# usb2.net
KiCad netlist of a schematic drawn in EAGLE
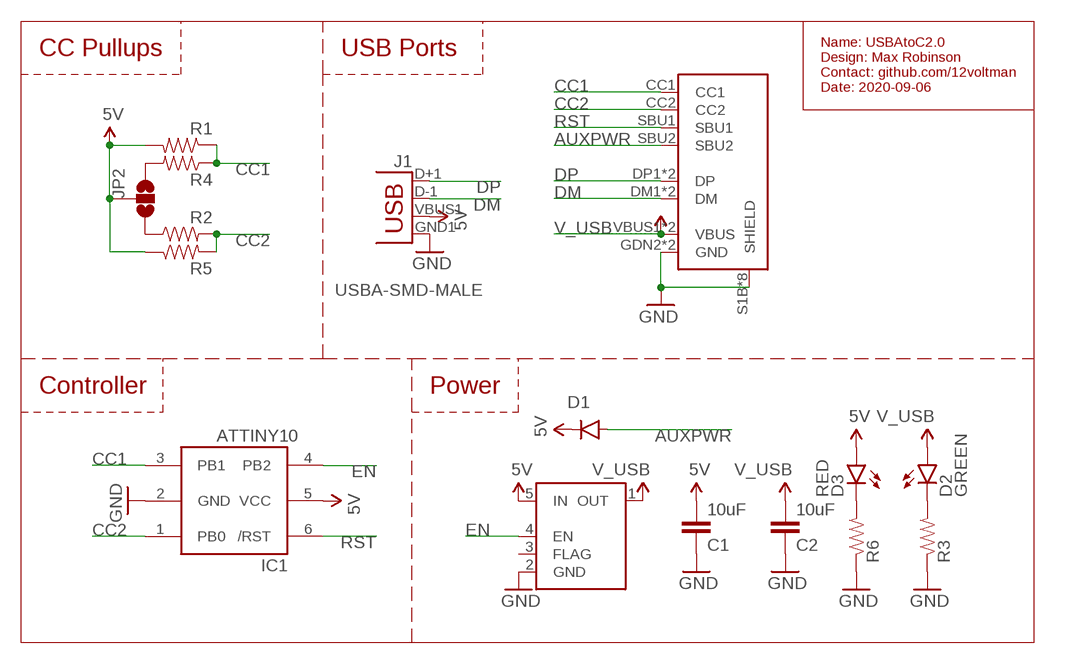
[diagram p0: schematic, sheet 1]

(export (version "E")
  (design (tool "Eeschema 10.0.6"))
  (components
    (comp (ref "C1")
      (value "10uF")
      (footprint "eagle-import:0603-CAP")
      (libsource (lib "eagle-import") (part "10UF-6.3V-20%(0603)"))
    )
    (comp (ref "C2")
      (value "10uF")
      (footprint "eagle-import:0603-CAP")
      (libsource (lib "eagle-import") (part "10UF-6.3V-20%(0603)"))
    )
    (comp (ref "D1")
      (value "250mA/100V")
      (footprint "eagle-import:SOD-323")
      (libsource (lib "eagle-import") (part "DIODEBAS16"))
    )
    (comp (ref "D2")
      (value "GREEN")
      (footprint "eagle-import:LED-0603")
      (libsource (lib "eagle-import") (part "LED-GREEN0603"))
    )
    (comp (ref "D3")
      (value "RED")
      (footprint "eagle-import:LED-0603")
      (libsource (lib "eagle-import") (part "LED-RED0603"))
    )
    (comp (ref "IC1")
      (value "ATTINY10")
      (footprint "eagle-import:SOT23-6")
      (libsource (lib "eagle-import") (part "ATTINY10"))
    )
    (comp (ref "J1")
      (value "USBA-SMD-MALE")
      (footprint "eagle-import:USB-A-SMT-MALE")
      (libsource (lib "eagle-import") (part "USBA-SMD-MALE"))
    )
    (comp (ref "JP2")
      (value "JUMPER-PAD-3-NOYES_SILK")
      (footprint "eagle-import:PAD-JUMPER-3-NO_YES_SILK")
      (libsource (lib "eagle-import") (part "JUMPER-PAD-3-NOYES_SILK"))
    )
    (comp (ref "R1")
      (value "RESISTOR0603")
      (footprint "eagle-import:0603-RES")
      (libsource (lib "eagle-import") (part "RESISTOR0603"))
    )
    (comp (ref "R2")
      (value "RESISTOR0603")
      (footprint "eagle-import:0603-RES")
      (libsource (lib "eagle-import") (part "RESISTOR0603"))
    )
    (comp (ref "R3")
      (value "RESISTOR0603")
      (footprint "eagle-import:0603-RES")
      (libsource (lib "eagle-import") (part "RESISTOR0603"))
    )
    (comp (ref "R4")
      (value "RESISTOR0603")
      (footprint "eagle-import:0603-RES")
      (libsource (lib "eagle-import") (part "RESISTOR0603"))
    )
    (comp (ref "R5")
      (value "RESISTOR0603")
      (footprint "eagle-import:0603-RES")
      (libsource (lib "eagle-import") (part "RESISTOR0603"))
    )
    (comp (ref "R6")
      (value "RESISTOR0603")
      (footprint "eagle-import:0603-RES")
      (libsource (lib "eagle-import") (part "RESISTOR0603"))
    )
    (comp (ref "U$1")
      (value "USB-C_USB2ONLY-OUTLINE")
      (footprint "eagle-import:USB-C_12PIN_HORZ-F-OUTLINE")
      (libsource (lib "eagle-import") (part "USB-C_USB2ONLY-OUTLINE"))
    )
    (comp (ref "U$2")
      (value "AP22804/14*W5-7")
      (footprint "eagle-import:SOT23-5")
      (libsource (lib "eagle-import") (part "AP22804/14W5-7"))
    )
  )
  (nets
    (net (code "1") (name "/AUXPWR") (class "Default")
      (node (ref "D1") (pin "A") (pinfunction "A_A") (pintype "passive"))
      (node (ref "U$1") (pin "SBU2") (pinfunction "SBU2_SBU2") (pintype "bidirectional"))
    )
    (net (code "2") (name "/CC1") (class "Default")
      (node (ref "IC1") (pin "3") (pinfunction "PB1_3") (pintype "bidirectional"))
      (node (ref "R1") (pin "1") (pinfunction "1_1") (pintype "passive"))
      (node (ref "R4") (pin "1") (pinfunction "1_1") (pintype "passive"))
      (node (ref "U$1") (pin "CC1") (pinfunction "CC1_CC1") (pintype "bidirectional"))
    )
    (net (code "3") (name "/CC2") (class "Default")
      (node (ref "IC1") (pin "1") (pinfunction "PB0_1") (pintype "bidirectional"))
      (node (ref "R2") (pin "2") (pinfunction "2_2") (pintype "passive"))
      (node (ref "R5") (pin "2") (pinfunction "2_2") (pintype "passive"))
      (node (ref "U$1") (pin "CC2") (pinfunction "CC2_CC2") (pintype "bidirectional"))
    )
    (net (code "4") (name "/DM") (class "Default")
      (node (ref "J1") (pin "D-1") (pinfunction "D-_D-1") (pintype "bidirectional"))
      (node (ref "U$1") (pin "DM1") (pinfunction "DM_DM1") (pintype "bidirectional"))
      (node (ref "U$1") (pin "DM2") (pinfunction "DM_DM2") (pintype "bidirectional"))
    )
    (net (code "5") (name "/DP") (class "Default")
      (node (ref "J1") (pin "D+1") (pinfunction "D+_D+1") (pintype "bidirectional"))
      (node (ref "U$1") (pin "DP1") (pinfunction "DP_DP1") (pintype "bidirectional"))
      (node (ref "U$1") (pin "DP2") (pinfunction "DP_DP2") (pintype "bidirectional"))
    )
    (net (code "6") (name "/EN") (class "Default")
      (node (ref "IC1") (pin "4") (pinfunction "PB2_4") (pintype "bidirectional"))
      (node (ref "U$2") (pin "4") (pinfunction "EN_4") (pintype "bidirectional"))
    )
    (net (code "7") (name "/RST") (class "Default")
      (node (ref "IC1") (pin "6") (pinfunction "/RST_6") (pintype "bidirectional"))
      (node (ref "U$1") (pin "SBU1") (pinfunction "SBU1_SBU1") (pintype "bidirectional"))
    )
    (net (code "8") (name "5V") (class "Default")
      (node (ref "C1") (pin "2") (pinfunction "2_2") (pintype "passive"))
      (node (ref "D1") (pin "C") (pinfunction "C_C") (pintype "passive"))
      (node (ref "D3") (pin "A") (pinfunction "A_A") (pintype "passive"))
      (node (ref "IC1") (pin "5") (pinfunction "VCC_5") (pintype "power_in"))
      (node (ref "J1") (pin "VBUS1") (pinfunction "VBUS_VBUS1") (pintype "bidirectional"))
      (node (ref "JP2") (pin "2") (pinfunction "2_2") (pintype "passive"))
      (node (ref "R1") (pin "2") (pinfunction "2_2") (pintype "passive"))
      (node (ref "R5") (pin "1") (pinfunction "1_1") (pintype "passive"))
      (node (ref "U$2") (pin "5") (pinfunction "IN_5") (pintype "bidirectional"))
    )
    (net (code "9") (name "GND") (class "Default")
      (node (ref "C1") (pin "1") (pinfunction "1_1") (pintype "passive"))
      (node (ref "C2") (pin "1") (pinfunction "1_1") (pintype "passive"))
      (node (ref "IC1") (pin "2") (pinfunction "GND_2") (pintype "power_in"))
      (node (ref "J1") (pin "GND1") (pinfunction "GND_GND1") (pintype "bidirectional"))
      (node (ref "R3") (pin "1") (pinfunction "1_1") (pintype "passive"))
      (node (ref "R6") (pin "1") (pinfunction "1_1") (pintype "passive"))
      (node (ref "U$1") (pin "GDN2") (pinfunction "GND_GDN2") (pintype "bidirectional"))
      (node (ref "U$1") (pin "GND1") (pinfunction "GND_GND1") (pintype "bidirectional"))
      (node (ref "U$1") (pin "S1B") (pinfunction "SHIELD_S1B") (pintype "bidirectional"))
      (node (ref "U$1") (pin "S1T") (pinfunction "SHIELD_S1T") (pintype "bidirectional"))
      (node (ref "U$1") (pin "S2B") (pinfunction "SHIELD_S2B") (pintype "bidirectional"))
      (node (ref "U$1") (pin "S2T") (pinfunction "SHIELD_S2T") (pintype "bidirectional"))
      (node (ref "U$1") (pin "S3B") (pinfunction "SHIELD_S3B") (pintype "bidirectional"))
      (node (ref "U$1") (pin "S3T") (pinfunction "SHIELD_S3T") (pintype "bidirectional"))
      (node (ref "U$1") (pin "S4B") (pinfunction "SHIELD_S4B") (pintype "bidirectional"))
      (node (ref "U$1") (pin "S4T") (pinfunction "SHIELD_S4T") (pintype "bidirectional"))
      (node (ref "U$2") (pin "2") (pinfunction "GND_2") (pintype "bidirectional"))
    )
    (net (code "10") (name "Net-(D2-PadC)") (class "Default")
      (node (ref "D2") (pin "C") (pinfunction "C_C") (pintype "passive"))
      (node (ref "R3") (pin "2") (pinfunction "2_2") (pintype "passive"))
    )
    (net (code "11") (name "Net-(D3-PadC)") (class "Default")
      (node (ref "D3") (pin "C") (pinfunction "C_C") (pintype "passive"))
      (node (ref "R6") (pin "2") (pinfunction "2_2") (pintype "passive"))
    )
    (net (code "12") (name "Net-(JP2-Pad1)") (class "Default")
      (node (ref "JP2") (pin "1") (pinfunction "1_1") (pintype "passive"))
      (node (ref "R4") (pin "2") (pinfunction "2_2") (pintype "passive"))
    )
    (net (code "13") (name "Net-(JP2-Pad3)") (class "Default")
      (node (ref "JP2") (pin "3") (pinfunction "3_3") (pintype "passive"))
      (node (ref "R2") (pin "1") (pinfunction "1_1") (pintype "passive"))
    )
    (net (code "14") (name "V_USB") (class "Default")
      (node (ref "C2") (pin "2") (pinfunction "2_2") (pintype "passive"))
      (node (ref "D2") (pin "A") (pinfunction "A_A") (pintype "passive"))
      (node (ref "U$1") (pin "VBUS1") (pinfunction "VBUS_VBUS1") (pintype "bidirectional"))
      (node (ref "U$1") (pin "VBUS2") (pinfunction "VBUS_VBUS2") (pintype "bidirectional"))
      (node (ref "U$2") (pin "1") (pinfunction "OUT_1") (pintype "bidirectional"))
    )
    (net (code "15") (name "unconnected-(U$2-FLAG-Pad3)") (class "Default")
      (node (ref "U$2") (pin "3") (pinfunction "FLAG_3") (pintype "bidirectional"))
    )
  )
)
